# twinklr_board.net
KiCad netlist of a schematic drawn in EAGLE
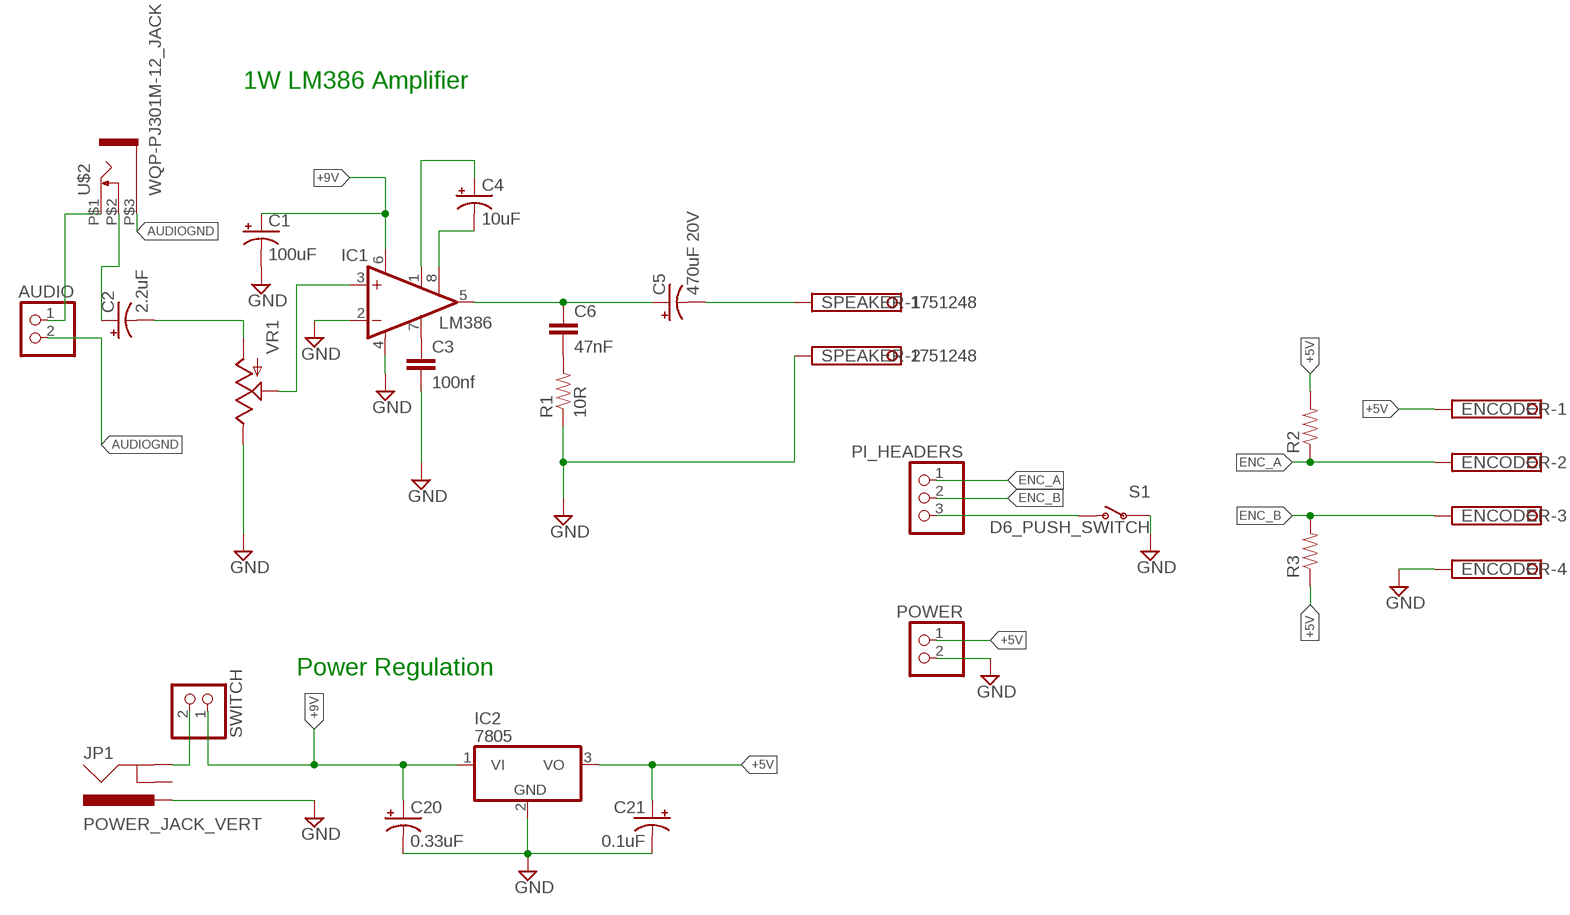
[diagram p0: schematic, sheet 1]

(export (version "E")
  (design (tool "Eeschema 10.0.6"))
  (components
    (comp (ref "AUDIO")
      (value "PINHD-1X2")
      (footprint "eagle-import:1X02")
      (libsource (lib "eagle-import") (part "PINHD-1X2"))
    )
    (comp (ref "C1")
      (value "100uF")
      (footprint "eagle-import:CPOL-RADIAL-10UF-25V")
      (libsource (lib "eagle-import") (part "CAP_POLPTH2"))
    )
    (comp (ref "C2")
      (value "2.2uF")
      (footprint "eagle-import:CPOL-RADIAL-10UF-25V")
      (libsource (lib "eagle-import") (part "CAP_POLPTH2"))
    )
    (comp (ref "C3")
      (value "100nf")
      (footprint "eagle-import:CAP-PTH-SMALL")
      (libsource (lib "eagle-import") (part "CAPPTH"))
    )
    (comp (ref "C4")
      (value "10uF")
      (footprint "eagle-import:CPOL-RADIAL-10UF-25V")
      (libsource (lib "eagle-import") (part "CAP_POLPTH2"))
    )
    (comp (ref "C5")
      (value "470uF 20V")
      (footprint "eagle-import:CPOL-RADIAL-1000UF-25V")
      (libsource (lib "eagle-import") (part "CAP_POLPTH4"))
    )
    (comp (ref "C6")
      (value "47nF")
      (footprint "eagle-import:AXIAL-5MM")
      (libsource (lib "eagle-import") (part "CAP_"))
    )
    (comp (ref "C20")
      (value "0.33uF")
      (footprint "eagle-import:CPOL-RADIAL-10UF-25V")
      (libsource (lib "eagle-import") (part "CAP_POLPTH2"))
    )
    (comp (ref "C21")
      (value "0.1uF")
      (footprint "eagle-import:CPOL-RADIAL-10UF-25V")
      (libsource (lib "eagle-import") (part "CAP_POLPTH2"))
    )
    (comp (ref "ENCODER")
      (value "1751264")
      (footprint "eagle-import:1751264")
      (libsource (lib "eagle-import") (part "1751264"))
    )
    (comp (ref "IC1")
      (value "LM386")
      (footprint "eagle-import:DIL08")
      (libsource (lib "eagle-import") (part "LM386?-N1"))
    )
    (comp (ref "IC2")
      (value "7805")
      (footprint "eagle-import:TO220V")
      (libsource (lib "eagle-import") (part "78TV05"))
    )
    (comp (ref "JP1")
      (value "POWER_JACK_VERT")
      (footprint "eagle-import:POWER_JACK_VERT")
      (libsource (lib "eagle-import") (part "POWER_JACK_VERT"))
    )
    (comp (ref "PI_HEADERS")
      (value "PINHD-1X3")
      (footprint "eagle-import:1X03")
      (libsource (lib "eagle-import") (part "PINHD-1X3"))
    )
    (comp (ref "POWER")
      (value "PINHD-1X2")
      (footprint "eagle-import:1X02")
      (libsource (lib "eagle-import") (part "PINHD-1X2"))
    )
    (comp (ref "R1")
      (value "10R")
      (footprint "eagle-import:AXIAL-0.3")
      (libsource (lib "eagle-import") (part "RESISTORAXIAL-0.3"))
    )
    (comp (ref "R2")
      (value "RESISTORAXIAL-0.3")
      (footprint "eagle-import:AXIAL-0.3")
      (libsource (lib "eagle-import") (part "RESISTORAXIAL-0.3"))
    )
    (comp (ref "R3")
      (value "RESISTORAXIAL-0.3")
      (footprint "eagle-import:AXIAL-0.3")
      (libsource (lib "eagle-import") (part "RESISTORAXIAL-0.3"))
    )
    (comp (ref "S1")
      (value "D6_PUSH_SWITCH")
      (footprint "eagle-import:D6_PUSH_SWITCH")
      (libsource (lib "eagle-import") (part "D6_PUSH_SWITCH"))
    )
    (comp (ref "SPEAKER")
      (value "1751248")
      (footprint "eagle-import:1751248")
      (libsource (lib "eagle-import") (part "1751248"))
    )
    (comp (ref "SWITCH")
      (value "PINHD-1X2")
      (footprint "eagle-import:1X02")
      (libsource (lib "eagle-import") (part "PINHD-1X2"))
    )
    (comp (ref "U$2")
      (value "WQP-PJ301M-12_JACK")
      (footprint "eagle-import:WQP-PJ301M-12_JACK")
      (libsource (lib "eagle-import") (part "WQP-PJ301M-12_JACK"))
    )
    (comp (ref "VR1")
      (value "POT")
      (footprint "eagle-import:ALPS_POT")
      (libsource (lib "eagle-import") (part "POT"))
    )
  )
  (nets
    (net (code "1") (name "+5V") (class "Default")
      (node (ref "C21") (pin "1") (pinfunction "+_1") (pintype "passive"))
      (node (ref "ENCODER") (pin "1") (pinfunction "K_1") (pintype "passive"))
      (node (ref "IC2") (pin "3") (pinfunction "VO_3") (pintype "passive"))
      (node (ref "POWER") (pin "1") (pinfunction "1_1") (pintype "passive"))
      (node (ref "R2") (pin "P$2") (pinfunction "2_P$2") (pintype "passive"))
      (node (ref "R3") (pin "P$1") (pinfunction "1_P$1") (pintype "passive"))
    )
    (net (code "2") (name "+9V") (class "Default")
      (node (ref "C1") (pin "1") (pinfunction "+_1") (pintype "passive"))
      (node (ref "C20") (pin "1") (pinfunction "+_1") (pintype "passive"))
      (node (ref "IC1") (pin "6") (pinfunction "VS_6") (pintype "power_in"))
      (node (ref "IC2") (pin "1") (pinfunction "VI_1") (pintype "input"))
      (node (ref "SWITCH") (pin "1") (pinfunction "1_1") (pintype "passive"))
    )
    (net (code "3") (name "AUDIOGND") (class "Default")
      (node (ref "AUDIO") (pin "2") (pinfunction "2_2") (pintype "passive"))
      (node (ref "U$2") (pin "P$3") (pinfunction "1_P$3") (pintype "passive"))
    )
    (net (code "4") (name "ENC_A") (class "Default")
      (node (ref "ENCODER") (pin "2") (pinfunction "K_2") (pintype "passive"))
      (node (ref "PI_HEADERS") (pin "1") (pinfunction "1_1") (pintype "passive"))
      (node (ref "R2") (pin "P$1") (pinfunction "1_P$1") (pintype "passive"))
    )
    (net (code "5") (name "ENC_B") (class "Default")
      (node (ref "ENCODER") (pin "3") (pinfunction "K_3") (pintype "passive"))
      (node (ref "PI_HEADERS") (pin "2") (pinfunction "2_2") (pintype "passive"))
      (node (ref "R3") (pin "P$2") (pinfunction "2_P$2") (pintype "passive"))
    )
    (net (code "6") (name "GND") (class "Default")
      (node (ref "C1") (pin "2") (pinfunction "-_2") (pintype "passive"))
      (node (ref "C20") (pin "2") (pinfunction "-_2") (pintype "passive"))
      (node (ref "C21") (pin "2") (pinfunction "-_2") (pintype "passive"))
      (node (ref "C3") (pin "2") (pinfunction "2_2") (pintype "passive"))
      (node (ref "ENCODER") (pin "4") (pinfunction "K_4") (pintype "passive"))
      (node (ref "IC1") (pin "2") (pinfunction "-IN_2") (pintype "input"))
      (node (ref "IC1") (pin "4") (pinfunction "GND_4") (pintype "power_in"))
      (node (ref "IC2") (pin "2") (pinfunction "GND_2") (pintype "passive"))
      (node (ref "JP1") (pin "PWR") (pinfunction "PWR_PWR") (pintype "bidirectional"))
      (node (ref "POWER") (pin "2") (pinfunction "2_2") (pintype "passive"))
      (node (ref "R1") (pin "P$1") (pinfunction "1_P$1") (pintype "passive"))
      (node (ref "S1") (pin "P$3") (pinfunction "P_P$3") (pintype "passive"))
      (node (ref "S1") (pin "P$4") (pinfunction "P_P$4") (pintype "passive"))
      (node (ref "SPEAKER") (pin "2") (pinfunction "K_2") (pintype "passive"))
      (node (ref "VR1") (pin "P$1") (pinfunction "E_P$1") (pintype "passive"))
    )
    (net (code "7") (name "Net-(C2-+)") (class "Default")
      (node (ref "C2") (pin "1") (pinfunction "+_1") (pintype "passive"))
      (node (ref "U$2") (pin "P$2") (pinfunction "3_P$2") (pintype "passive"))
    )
    (net (code "8") (name "Net-(C2--)") (class "Default")
      (node (ref "C2") (pin "2") (pinfunction "-_2") (pintype "passive"))
      (node (ref "VR1") (pin "P$3") (pinfunction "A_P$3") (pintype "passive"))
    )
    (net (code "9") (name "Net-(C4-+)") (class "Default")
      (node (ref "C4") (pin "1") (pinfunction "+_1") (pintype "passive"))
      (node (ref "IC1") (pin "1") (pinfunction "GAIN_1") (pintype "passive"))
    )
    (net (code "10") (name "Net-(C4--)") (class "Default")
      (node (ref "C4") (pin "2") (pinfunction "-_2") (pintype "passive"))
      (node (ref "IC1") (pin "8") (pinfunction "GAIN_8") (pintype "passive"))
    )
    (net (code "11") (name "Net-(C6-1)") (class "Default")
      (node (ref "C5") (pin "+") (pinfunction "+_+") (pintype "passive"))
      (node (ref "C6") (pin "P$1") (pinfunction "1_P$1") (pintype "passive"))
      (node (ref "IC1") (pin "5") (pinfunction "OUT_5") (pintype "output"))
    )
    (net (code "12") (name "Net-(C6-2)") (class "Default")
      (node (ref "C6") (pin "P$2") (pinfunction "2_P$2") (pintype "passive"))
      (node (ref "R1") (pin "P$2") (pinfunction "2_P$2") (pintype "passive"))
    )
    (net (code "13") (name "Net-(IC1-+IN)") (class "Default")
      (node (ref "IC1") (pin "3") (pinfunction "+IN_3") (pintype "input"))
      (node (ref "VR1") (pin "P$2") (pinfunction "S_P$2") (pintype "passive"))
    )
    (net (code "14") (name "Net-(IC1-BYPASS)") (class "Default")
      (node (ref "C3") (pin "1") (pinfunction "1_1") (pintype "passive"))
      (node (ref "IC1") (pin "7") (pinfunction "BYPASS_7") (pintype "passive"))
    )
    (net (code "15") (name "Net-(JP1-PadGND)") (class "Default")
      (node (ref "JP1") (pin "GND") (pinfunction "GND_GND") (pintype "bidirectional"))
      (node (ref "SWITCH") (pin "2") (pinfunction "2_2") (pintype "passive"))
    )
    (net (code "16") (name "Net-(PI_HEADERS-Pad3)") (class "Default")
      (node (ref "PI_HEADERS") (pin "3") (pinfunction "3_3") (pintype "passive"))
      (node (ref "S1") (pin "P$1") (pinfunction "O_P$1") (pintype "passive"))
      (node (ref "S1") (pin "P$2") (pinfunction "O_P$2") (pintype "passive"))
    )
    (net (code "17") (name "Net-(SPEAKERA-K)") (class "Default")
      (node (ref "C5") (pin "-") (pinfunction "-_-") (pintype "passive"))
      (node (ref "SPEAKER") (pin "1") (pinfunction "K_1") (pintype "passive"))
    )
    (net (code "18") (name "Net-(U$2-2)") (class "Default")
      (node (ref "AUDIO") (pin "1") (pinfunction "1_1") (pintype "passive"))
      (node (ref "U$2") (pin "P$1") (pinfunction "2_P$1") (pintype "passive"))
    )
    (net (code "19") (name "unconnected-(JP1-PadGNDBREAK)") (class "Default")
      (node (ref "JP1") (pin "GNDBREAK") (pinfunction "GNDBREAK_GNDBREAK") (pintype "bidirectional"))
    )
  )
)
